# 003.net
KiCad netlist of a schematic drawn in EAGLE
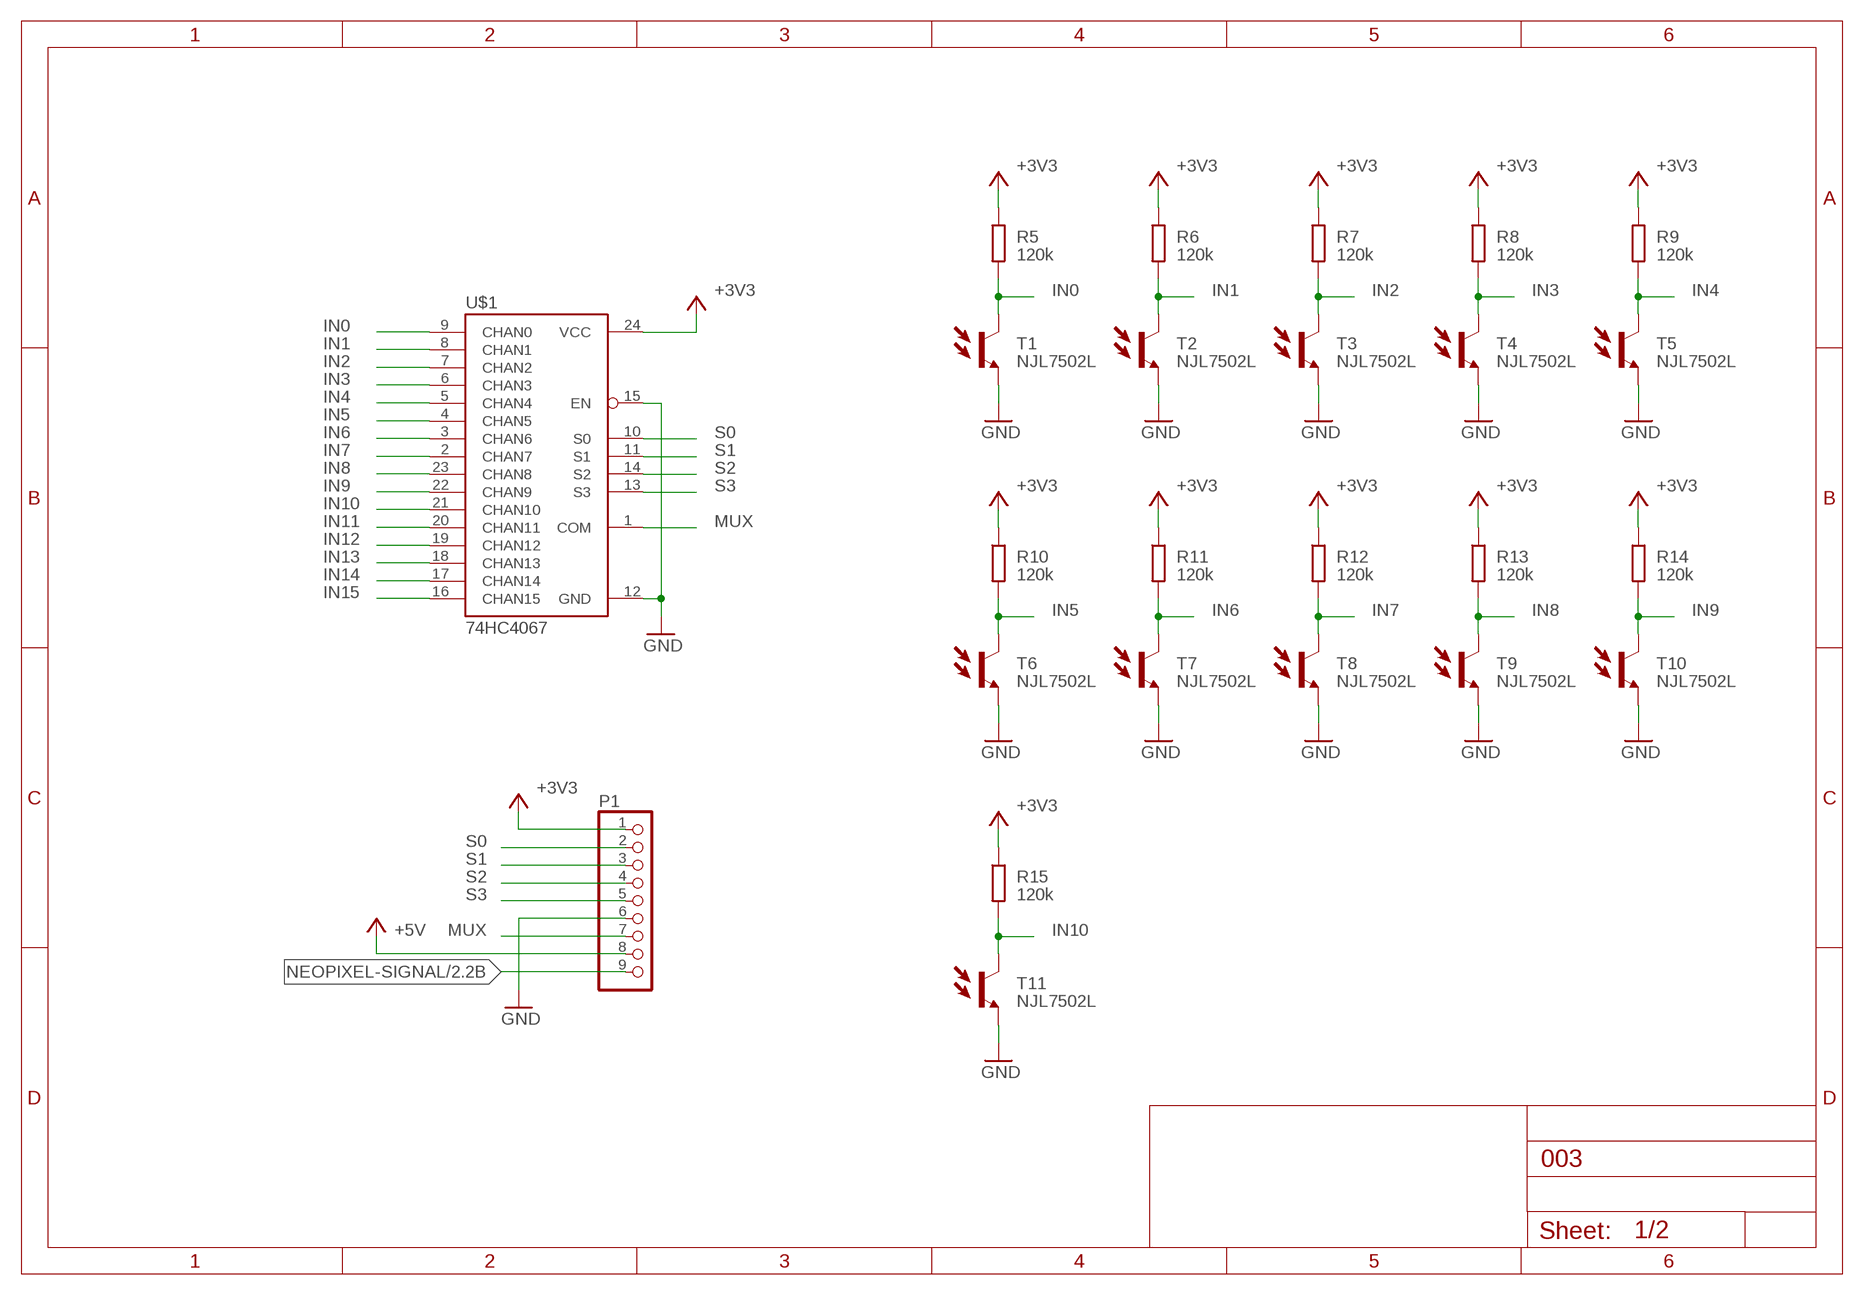
[diagram p0: schematic, sheet 1]
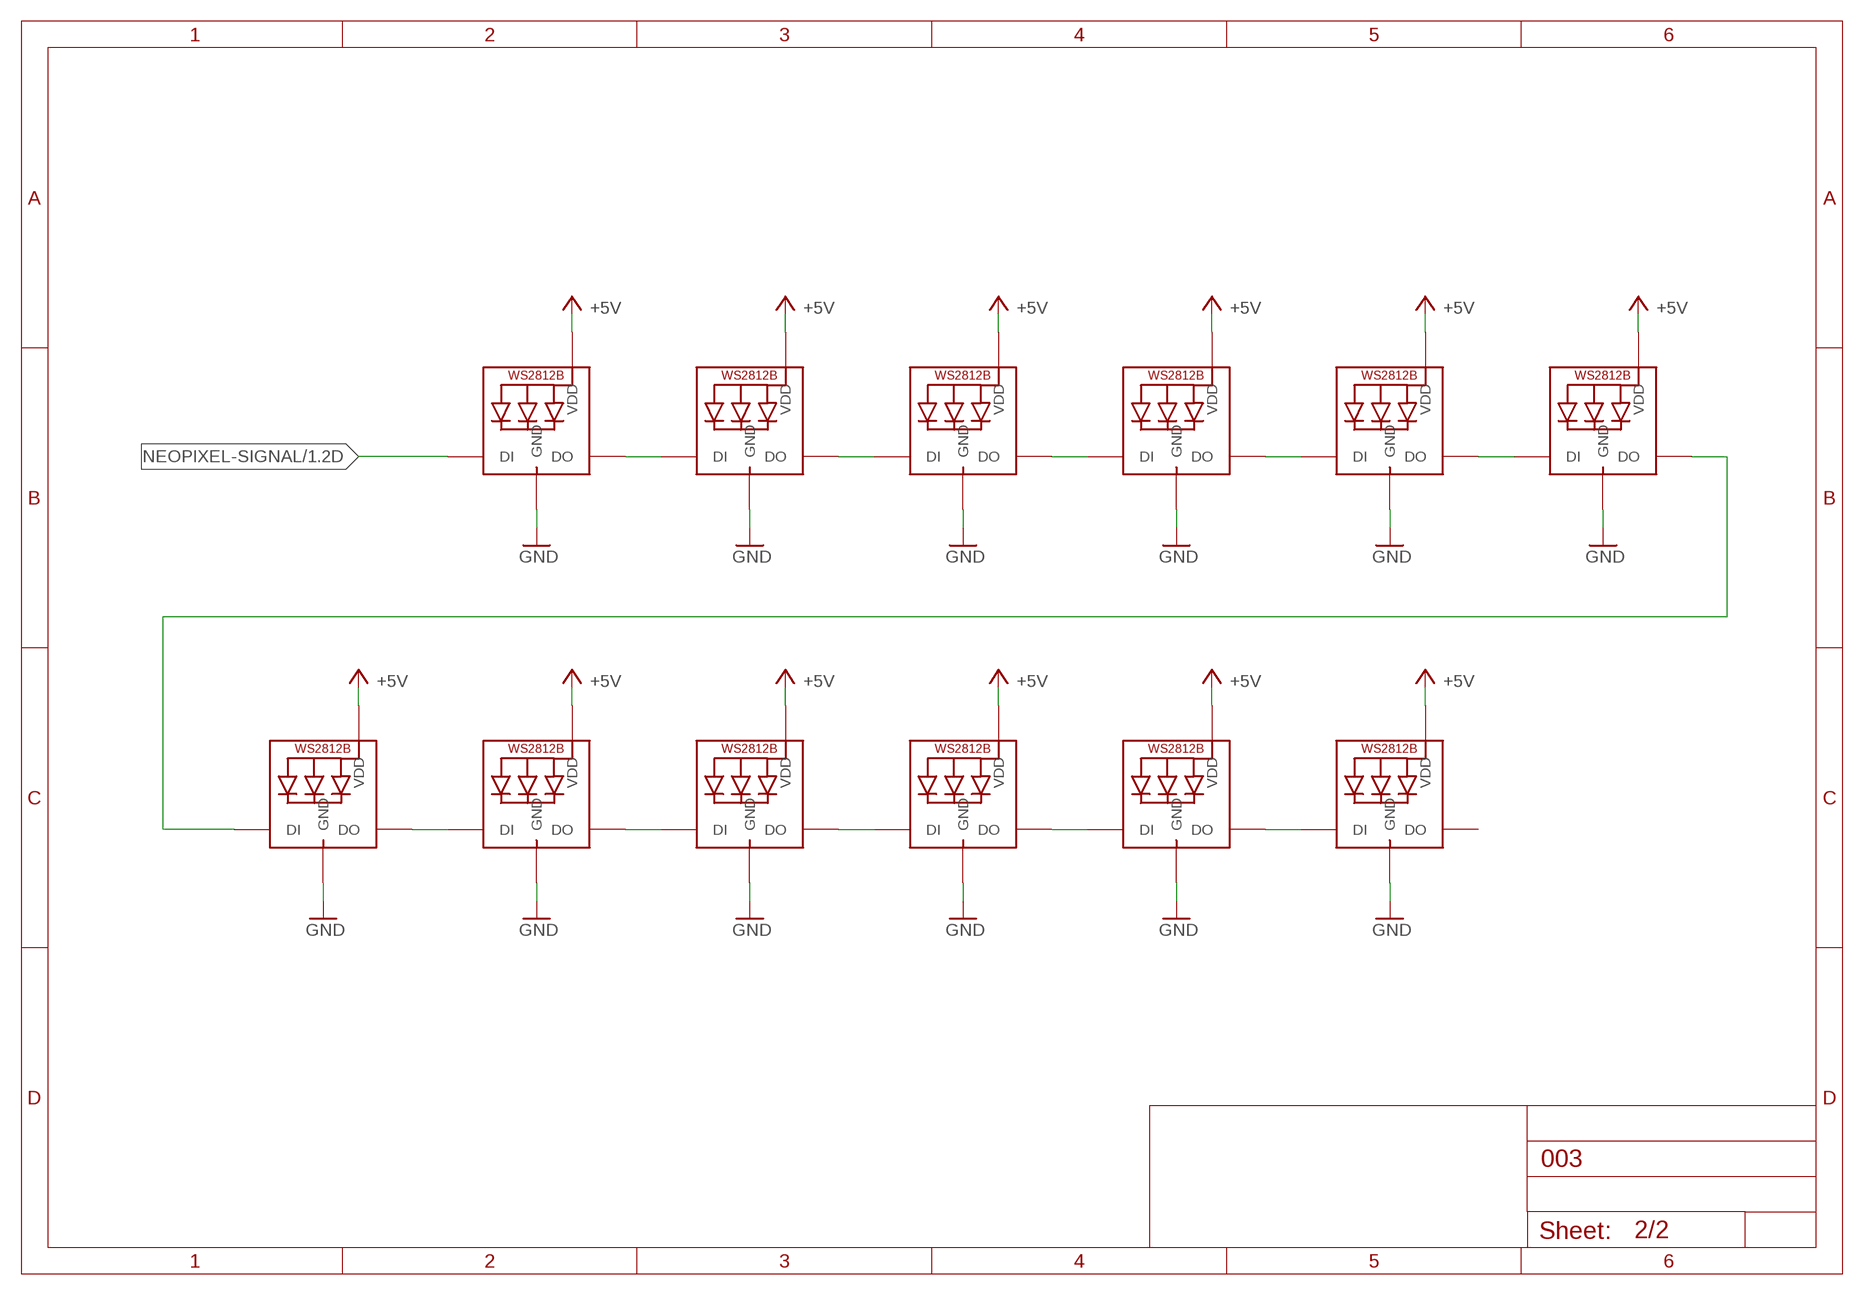
[diagram p1: schematic, sheet 2]

(export (version "E")
  (design (tool "Eeschema 10.0.6"))
  (components
    (comp (ref "P1")
      (value "S9B-ZR-SM4A-TF")
      (footprint "eagle-import:ZH-SM4-SIDE09")
      (libsource (lib "eagle-import") (part "S9B-ZR-SM4A-TF"))
    )
    (comp (ref "R5")
      (value "120k")
      (footprint "eagle-import:R0805")
      (libsource (lib "eagle-import") (part "R-EU_R0805"))
    )
    (comp (ref "R6")
      (value "120k")
      (footprint "eagle-import:R0805")
      (libsource (lib "eagle-import") (part "R-EU_R0805"))
    )
    (comp (ref "R7")
      (value "120k")
      (footprint "eagle-import:R0805")
      (libsource (lib "eagle-import") (part "R-EU_R0805"))
    )
    (comp (ref "R8")
      (value "120k")
      (footprint "eagle-import:R0805")
      (libsource (lib "eagle-import") (part "R-EU_R0805"))
    )
    (comp (ref "R9")
      (value "120k")
      (footprint "eagle-import:R0805")
      (libsource (lib "eagle-import") (part "R-EU_R0805"))
    )
    (comp (ref "R10")
      (value "120k")
      (footprint "eagle-import:R0805")
      (libsource (lib "eagle-import") (part "R-EU_R0805"))
    )
    (comp (ref "R11")
      (value "120k")
      (footprint "eagle-import:R0805")
      (libsource (lib "eagle-import") (part "R-EU_R0805"))
    )
    (comp (ref "R12")
      (value "120k")
      (footprint "eagle-import:R0805")
      (libsource (lib "eagle-import") (part "R-EU_R0805"))
    )
    (comp (ref "R13")
      (value "120k")
      (footprint "eagle-import:R0805")
      (libsource (lib "eagle-import") (part "R-EU_R0805"))
    )
    (comp (ref "R14")
      (value "120k")
      (footprint "eagle-import:R0805")
      (libsource (lib "eagle-import") (part "R-EU_R0805"))
    )
    (comp (ref "R15")
      (value "120k")
      (footprint "eagle-import:R0805")
      (libsource (lib "eagle-import") (part "R-EU_R0805"))
    )
    (comp (ref "T1")
      (value "NJL7502L")
      (footprint "eagle-import:MYPARTS_NJL7502L")
      (libsource (lib "eagle-import") (part "MYPARTS_NJL7502L"))
    )
    (comp (ref "T2")
      (value "NJL7502L")
      (footprint "eagle-import:MYPARTS_NJL7502L")
      (libsource (lib "eagle-import") (part "MYPARTS_NJL7502L"))
    )
    (comp (ref "T3")
      (value "NJL7502L")
      (footprint "eagle-import:MYPARTS_NJL7502L")
      (libsource (lib "eagle-import") (part "MYPARTS_NJL7502L"))
    )
    (comp (ref "T4")
      (value "NJL7502L")
      (footprint "eagle-import:MYPARTS_NJL7502L")
      (libsource (lib "eagle-import") (part "MYPARTS_NJL7502L"))
    )
    (comp (ref "T5")
      (value "NJL7502L")
      (footprint "eagle-import:MYPARTS_NJL7502L")
      (libsource (lib "eagle-import") (part "MYPARTS_NJL7502L"))
    )
    (comp (ref "T6")
      (value "NJL7502L")
      (footprint "eagle-import:MYPARTS_NJL7502L")
      (libsource (lib "eagle-import") (part "MYPARTS_NJL7502L"))
    )
    (comp (ref "T7")
      (value "NJL7502L")
      (footprint "eagle-import:MYPARTS_NJL7502L")
      (libsource (lib "eagle-import") (part "MYPARTS_NJL7502L"))
    )
    (comp (ref "T8")
      (value "NJL7502L")
      (footprint "eagle-import:MYPARTS_NJL7502L")
      (libsource (lib "eagle-import") (part "MYPARTS_NJL7502L"))
    )
    (comp (ref "T9")
      (value "NJL7502L")
      (footprint "eagle-import:MYPARTS_NJL7502L")
      (libsource (lib "eagle-import") (part "MYPARTS_NJL7502L"))
    )
    (comp (ref "T10")
      (value "NJL7502L")
      (footprint "eagle-import:MYPARTS_NJL7502L")
      (libsource (lib "eagle-import") (part "MYPARTS_NJL7502L"))
    )
    (comp (ref "T11")
      (value "NJL7502L")
      (footprint "eagle-import:MYPARTS_NJL7502L")
      (libsource (lib "eagle-import") (part "MYPARTS_NJL7502L"))
    )
    (comp (ref "U$1")
      (value "74HC4067")
      (footprint "eagle-import:SPARKFUN_SSOP24")
      (libsource (lib "eagle-import") (part "SPARKFUN_MUX-74HC4067SMD"))
    )
    (comp (ref "LED1")
      (value "WS2812B5050")
      (footprint "eagle-import:WS2812B")
      (libsource (lib "eagle-import") (part "WS2812B5050"))
    )
    (comp (ref "LED2")
      (value "WS2812B5050")
      (footprint "eagle-import:WS2812B")
      (libsource (lib "eagle-import") (part "WS2812B5050"))
    )
    (comp (ref "LED3")
      (value "WS2812B5050")
      (footprint "eagle-import:WS2812B")
      (libsource (lib "eagle-import") (part "WS2812B5050"))
    )
    (comp (ref "LED4")
      (value "WS2812B5050")
      (footprint "eagle-import:WS2812B")
      (libsource (lib "eagle-import") (part "WS2812B5050"))
    )
    (comp (ref "LED5")
      (value "WS2812B5050")
      (footprint "eagle-import:WS2812B")
      (libsource (lib "eagle-import") (part "WS2812B5050"))
    )
    (comp (ref "LED6")
      (value "WS2812B5050")
      (footprint "eagle-import:WS2812B")
      (libsource (lib "eagle-import") (part "WS2812B5050"))
    )
    (comp (ref "LED7")
      (value "WS2812B5050")
      (footprint "eagle-import:WS2812B")
      (libsource (lib "eagle-import") (part "WS2812B5050"))
    )
    (comp (ref "LED8")
      (value "WS2812B5050")
      (footprint "eagle-import:WS2812B")
      (libsource (lib "eagle-import") (part "WS2812B5050"))
    )
    (comp (ref "LED9")
      (value "WS2812B5050")
      (footprint "eagle-import:WS2812B")
      (libsource (lib "eagle-import") (part "WS2812B5050"))
    )
    (comp (ref "LED10")
      (value "WS2812B5050")
      (footprint "eagle-import:WS2812B")
      (libsource (lib "eagle-import") (part "WS2812B5050"))
    )
    (comp (ref "LED11")
      (value "WS2812B5050")
      (footprint "eagle-import:WS2812B")
      (libsource (lib "eagle-import") (part "WS2812B5050"))
    )
    (comp (ref "LED12")
      (value "WS2812B5050")
      (footprint "eagle-import:WS2812B")
      (libsource (lib "eagle-import") (part "WS2812B5050"))
    )
  )
  (nets
    (net (code "1") (name "+3V3") (class "Default")
      (node (ref "P1") (pin "1") (pinfunction "1_1") (pintype "passive"))
      (node (ref "R10") (pin "1") (pinfunction "1_1") (pintype "passive"))
      (node (ref "R11") (pin "1") (pinfunction "1_1") (pintype "passive"))
      (node (ref "R12") (pin "1") (pinfunction "1_1") (pintype "passive"))
      (node (ref "R13") (pin "1") (pinfunction "1_1") (pintype "passive"))
      (node (ref "R14") (pin "1") (pinfunction "1_1") (pintype "passive"))
      (node (ref "R15") (pin "1") (pinfunction "1_1") (pintype "passive"))
      (node (ref "R5") (pin "1") (pinfunction "1_1") (pintype "passive"))
      (node (ref "R6") (pin "1") (pinfunction "1_1") (pintype "passive"))
      (node (ref "R7") (pin "1") (pinfunction "1_1") (pintype "passive"))
      (node (ref "R8") (pin "1") (pinfunction "1_1") (pintype "passive"))
      (node (ref "R9") (pin "1") (pinfunction "1_1") (pintype "passive"))
      (node (ref "U$1") (pin "24") (pinfunction "VCC_24") (pintype "bidirectional"))
    )
    (net (code "2") (name "+5V") (class "Default")
      (node (ref "LED1") (pin "1-VDD") (pinfunction "VDD_1-VDD") (pintype "power_in"))
      (node (ref "LED10") (pin "1-VDD") (pinfunction "VDD_1-VDD") (pintype "power_in"))
      (node (ref "LED11") (pin "1-VDD") (pinfunction "VDD_1-VDD") (pintype "power_in"))
      (node (ref "LED12") (pin "1-VDD") (pinfunction "VDD_1-VDD") (pintype "power_in"))
      (node (ref "LED2") (pin "1-VDD") (pinfunction "VDD_1-VDD") (pintype "power_in"))
      (node (ref "LED3") (pin "1-VDD") (pinfunction "VDD_1-VDD") (pintype "power_in"))
      (node (ref "LED4") (pin "1-VDD") (pinfunction "VDD_1-VDD") (pintype "power_in"))
      (node (ref "LED5") (pin "1-VDD") (pinfunction "VDD_1-VDD") (pintype "power_in"))
      (node (ref "LED6") (pin "1-VDD") (pinfunction "VDD_1-VDD") (pintype "power_in"))
      (node (ref "LED7") (pin "1-VDD") (pinfunction "VDD_1-VDD") (pintype "power_in"))
      (node (ref "LED8") (pin "1-VDD") (pinfunction "VDD_1-VDD") (pintype "power_in"))
      (node (ref "LED9") (pin "1-VDD") (pinfunction "VDD_1-VDD") (pintype "power_in"))
      (node (ref "P1") (pin "8") (pinfunction "8_8") (pintype "passive"))
    )
    (net (code "3") (name "GND") (class "Default")
      (node (ref "LED1") (pin "3-GND") (pinfunction "GND_3-GND") (pintype "power_in"))
      (node (ref "LED10") (pin "3-GND") (pinfunction "GND_3-GND") (pintype "power_in"))
      (node (ref "LED11") (pin "3-GND") (pinfunction "GND_3-GND") (pintype "power_in"))
      (node (ref "LED12") (pin "3-GND") (pinfunction "GND_3-GND") (pintype "power_in"))
      (node (ref "LED2") (pin "3-GND") (pinfunction "GND_3-GND") (pintype "power_in"))
      (node (ref "LED3") (pin "3-GND") (pinfunction "GND_3-GND") (pintype "power_in"))
      (node (ref "LED4") (pin "3-GND") (pinfunction "GND_3-GND") (pintype "power_in"))
      (node (ref "LED5") (pin "3-GND") (pinfunction "GND_3-GND") (pintype "power_in"))
      (node (ref "LED6") (pin "3-GND") (pinfunction "GND_3-GND") (pintype "power_in"))
      (node (ref "LED7") (pin "3-GND") (pinfunction "GND_3-GND") (pintype "power_in"))
      (node (ref "LED8") (pin "3-GND") (pinfunction "GND_3-GND") (pintype "power_in"))
      (node (ref "LED9") (pin "3-GND") (pinfunction "GND_3-GND") (pintype "power_in"))
      (node (ref "P1") (pin "6") (pinfunction "6_6") (pintype "passive"))
      (node (ref "T1") (pin "E") (pinfunction "E_E") (pintype "passive"))
      (node (ref "T10") (pin "E") (pinfunction "E_E") (pintype "passive"))
      (node (ref "T11") (pin "E") (pinfunction "E_E") (pintype "passive"))
      (node (ref "T2") (pin "E") (pinfunction "E_E") (pintype "passive"))
      (node (ref "T3") (pin "E") (pinfunction "E_E") (pintype "passive"))
      (node (ref "T4") (pin "E") (pinfunction "E_E") (pintype "passive"))
      (node (ref "T5") (pin "E") (pinfunction "E_E") (pintype "passive"))
      (node (ref "T6") (pin "E") (pinfunction "E_E") (pintype "passive"))
      (node (ref "T7") (pin "E") (pinfunction "E_E") (pintype "passive"))
      (node (ref "T8") (pin "E") (pinfunction "E_E") (pintype "passive"))
      (node (ref "T9") (pin "E") (pinfunction "E_E") (pintype "passive"))
      (node (ref "U$1") (pin "12") (pinfunction "GND_12") (pintype "bidirectional"))
      (node (ref "U$1") (pin "15") (pinfunction "EN_15") (pintype "input"))
    )
    (net (code "4") (name "IN0") (class "Default")
      (node (ref "R5") (pin "2") (pinfunction "2_2") (pintype "passive"))
      (node (ref "T1") (pin "C") (pinfunction "C_C") (pintype "passive"))
      (node (ref "U$1") (pin "9") (pinfunction "CHAN0_9") (pintype "bidirectional"))
    )
    (net (code "5") (name "IN1") (class "Default")
      (node (ref "R6") (pin "2") (pinfunction "2_2") (pintype "passive"))
      (node (ref "T2") (pin "C") (pinfunction "C_C") (pintype "passive"))
      (node (ref "U$1") (pin "8") (pinfunction "CHAN1_8") (pintype "bidirectional"))
    )
    (net (code "6") (name "IN2") (class "Default")
      (node (ref "R7") (pin "2") (pinfunction "2_2") (pintype "passive"))
      (node (ref "T3") (pin "C") (pinfunction "C_C") (pintype "passive"))
      (node (ref "U$1") (pin "7") (pinfunction "CHAN2_7") (pintype "bidirectional"))
    )
    (net (code "7") (name "IN3") (class "Default")
      (node (ref "R8") (pin "2") (pinfunction "2_2") (pintype "passive"))
      (node (ref "T4") (pin "C") (pinfunction "C_C") (pintype "passive"))
      (node (ref "U$1") (pin "6") (pinfunction "CHAN3_6") (pintype "bidirectional"))
    )
    (net (code "8") (name "IN4") (class "Default")
      (node (ref "R9") (pin "2") (pinfunction "2_2") (pintype "passive"))
      (node (ref "T5") (pin "C") (pinfunction "C_C") (pintype "passive"))
      (node (ref "U$1") (pin "5") (pinfunction "CHAN4_5") (pintype "bidirectional"))
    )
    (net (code "9") (name "IN5") (class "Default")
      (node (ref "R10") (pin "2") (pinfunction "2_2") (pintype "passive"))
      (node (ref "T6") (pin "C") (pinfunction "C_C") (pintype "passive"))
      (node (ref "U$1") (pin "4") (pinfunction "CHAN5_4") (pintype "bidirectional"))
    )
    (net (code "10") (name "IN6") (class "Default")
      (node (ref "R11") (pin "2") (pinfunction "2_2") (pintype "passive"))
      (node (ref "T7") (pin "C") (pinfunction "C_C") (pintype "passive"))
      (node (ref "U$1") (pin "3") (pinfunction "CHAN6_3") (pintype "bidirectional"))
    )
    (net (code "11") (name "IN7") (class "Default")
      (node (ref "R12") (pin "2") (pinfunction "2_2") (pintype "passive"))
      (node (ref "T8") (pin "C") (pinfunction "C_C") (pintype "passive"))
      (node (ref "U$1") (pin "2") (pinfunction "CHAN7_2") (pintype "bidirectional"))
    )
    (net (code "12") (name "IN8") (class "Default")
      (node (ref "R13") (pin "2") (pinfunction "2_2") (pintype "passive"))
      (node (ref "T9") (pin "C") (pinfunction "C_C") (pintype "passive"))
      (node (ref "U$1") (pin "23") (pinfunction "CHAN8_23") (pintype "bidirectional"))
    )
    (net (code "13") (name "IN9") (class "Default")
      (node (ref "R14") (pin "2") (pinfunction "2_2") (pintype "passive"))
      (node (ref "T10") (pin "C") (pinfunction "C_C") (pintype "passive"))
      (node (ref "U$1") (pin "22") (pinfunction "CHAN9_22") (pintype "bidirectional"))
    )
    (net (code "14") (name "IN10") (class "Default")
      (node (ref "R15") (pin "2") (pinfunction "2_2") (pintype "passive"))
      (node (ref "T11") (pin "C") (pinfunction "C_C") (pintype "passive"))
      (node (ref "U$1") (pin "21") (pinfunction "CHAN10_21") (pintype "bidirectional"))
    )
    (net (code "15") (name "IN11") (class "Default")
      (node (ref "U$1") (pin "20") (pinfunction "CHAN11_20") (pintype "bidirectional"))
    )
    (net (code "16") (name "IN12") (class "Default")
      (node (ref "U$1") (pin "19") (pinfunction "CHAN12_19") (pintype "bidirectional"))
    )
    (net (code "17") (name "IN13") (class "Default")
      (node (ref "U$1") (pin "18") (pinfunction "CHAN13_18") (pintype "bidirectional"))
    )
    (net (code "18") (name "IN14") (class "Default")
      (node (ref "U$1") (pin "17") (pinfunction "CHAN14_17") (pintype "bidirectional"))
    )
    (net (code "19") (name "IN15") (class "Default")
      (node (ref "U$1") (pin "16") (pinfunction "CHAN15_16") (pintype "bidirectional"))
    )
    (net (code "20") (name "MUX") (class "Default")
      (node (ref "P1") (pin "7") (pinfunction "7_7") (pintype "passive"))
      (node (ref "U$1") (pin "1") (pinfunction "COM_1") (pintype "bidirectional"))
    )
    (net (code "21") (name "NEOPIXEL-SIGNAL") (class "Default")
      (node (ref "LED1") (pin "4-DIN") (pinfunction "DI_4-DIN") (pintype "input"))
      (node (ref "P1") (pin "9") (pinfunction "9_9") (pintype "passive"))
    )
    (net (code "22") (name "Net-(LED1-DO)") (class "Default")
      (node (ref "LED1") (pin "2-DOUT") (pinfunction "DO_2-DOUT") (pintype "output"))
      (node (ref "LED2") (pin "4-DIN") (pinfunction "DI_4-DIN") (pintype "input"))
    )
    (net (code "23") (name "Net-(LED2-DO)") (class "Default")
      (node (ref "LED2") (pin "2-DOUT") (pinfunction "DO_2-DOUT") (pintype "output"))
      (node (ref "LED3") (pin "4-DIN") (pinfunction "DI_4-DIN") (pintype "input"))
    )
    (net (code "24") (name "Net-(LED3-DO)") (class "Default")
      (node (ref "LED3") (pin "2-DOUT") (pinfunction "DO_2-DOUT") (pintype "output"))
      (node (ref "LED4") (pin "4-DIN") (pinfunction "DI_4-DIN") (pintype "input"))
    )
    (net (code "25") (name "Net-(LED4-DO)") (class "Default")
      (node (ref "LED4") (pin "2-DOUT") (pinfunction "DO_2-DOUT") (pintype "output"))
      (node (ref "LED5") (pin "4-DIN") (pinfunction "DI_4-DIN") (pintype "input"))
    )
    (net (code "26") (name "Net-(LED5-DO)") (class "Default")
      (node (ref "LED5") (pin "2-DOUT") (pinfunction "DO_2-DOUT") (pintype "output"))
      (node (ref "LED6") (pin "4-DIN") (pinfunction "DI_4-DIN") (pintype "input"))
    )
    (net (code "27") (name "Net-(LED6-DO)") (class "Default")
      (node (ref "LED6") (pin "2-DOUT") (pinfunction "DO_2-DOUT") (pintype "output"))
      (node (ref "LED7") (pin "4-DIN") (pinfunction "DI_4-DIN") (pintype "input"))
    )
    (net (code "28") (name "Net-(LED7-DO)") (class "Default")
      (node (ref "LED7") (pin "2-DOUT") (pinfunction "DO_2-DOUT") (pintype "output"))
      (node (ref "LED8") (pin "4-DIN") (pinfunction "DI_4-DIN") (pintype "input"))
    )
    (net (code "29") (name "Net-(LED8-DO)") (class "Default")
      (node (ref "LED8") (pin "2-DOUT") (pinfunction "DO_2-DOUT") (pintype "output"))
      (node (ref "LED9") (pin "4-DIN") (pinfunction "DI_4-DIN") (pintype "input"))
    )
    (net (code "30") (name "Net-(LED10-DI)") (class "Default")
      (node (ref "LED10") (pin "4-DIN") (pinfunction "DI_4-DIN") (pintype "input"))
      (node (ref "LED9") (pin "2-DOUT") (pinfunction "DO_2-DOUT") (pintype "output"))
    )
    (net (code "31") (name "Net-(LED10-DO)") (class "Default")
      (node (ref "LED10") (pin "2-DOUT") (pinfunction "DO_2-DOUT") (pintype "output"))
      (node (ref "LED11") (pin "4-DIN") (pinfunction "DI_4-DIN") (pintype "input"))
    )
    (net (code "32") (name "Net-(LED11-DO)") (class "Default")
      (node (ref "LED11") (pin "2-DOUT") (pinfunction "DO_2-DOUT") (pintype "output"))
      (node (ref "LED12") (pin "4-DIN") (pinfunction "DI_4-DIN") (pintype "input"))
    )
    (net (code "33") (name "S0") (class "Default")
      (node (ref "P1") (pin "2") (pinfunction "2_2") (pintype "passive"))
      (node (ref "U$1") (pin "10") (pinfunction "S0_10") (pintype "input"))
    )
    (net (code "34") (name "S1") (class "Default")
      (node (ref "P1") (pin "3") (pinfunction "3_3") (pintype "passive"))
      (node (ref "U$1") (pin "11") (pinfunction "S1_11") (pintype "input"))
    )
    (net (code "35") (name "S2") (class "Default")
      (node (ref "P1") (pin "4") (pinfunction "4_4") (pintype "passive"))
      (node (ref "U$1") (pin "14") (pinfunction "S2_14") (pintype "input"))
    )
    (net (code "36") (name "S3") (class "Default")
      (node (ref "P1") (pin "5") (pinfunction "5_5") (pintype "passive"))
      (node (ref "U$1") (pin "13") (pinfunction "S3_13") (pintype "input"))
    )
    (net (code "37") (name "unconnected-(LED12-DO-Pad2-DOUT)") (class "Default")
      (node (ref "LED12") (pin "2-DOUT") (pinfunction "DO_2-DOUT") (pintype "output"))
    )
  )
)
